# Hovilink.net
KiCad netlist of a schematic drawn in EAGLE
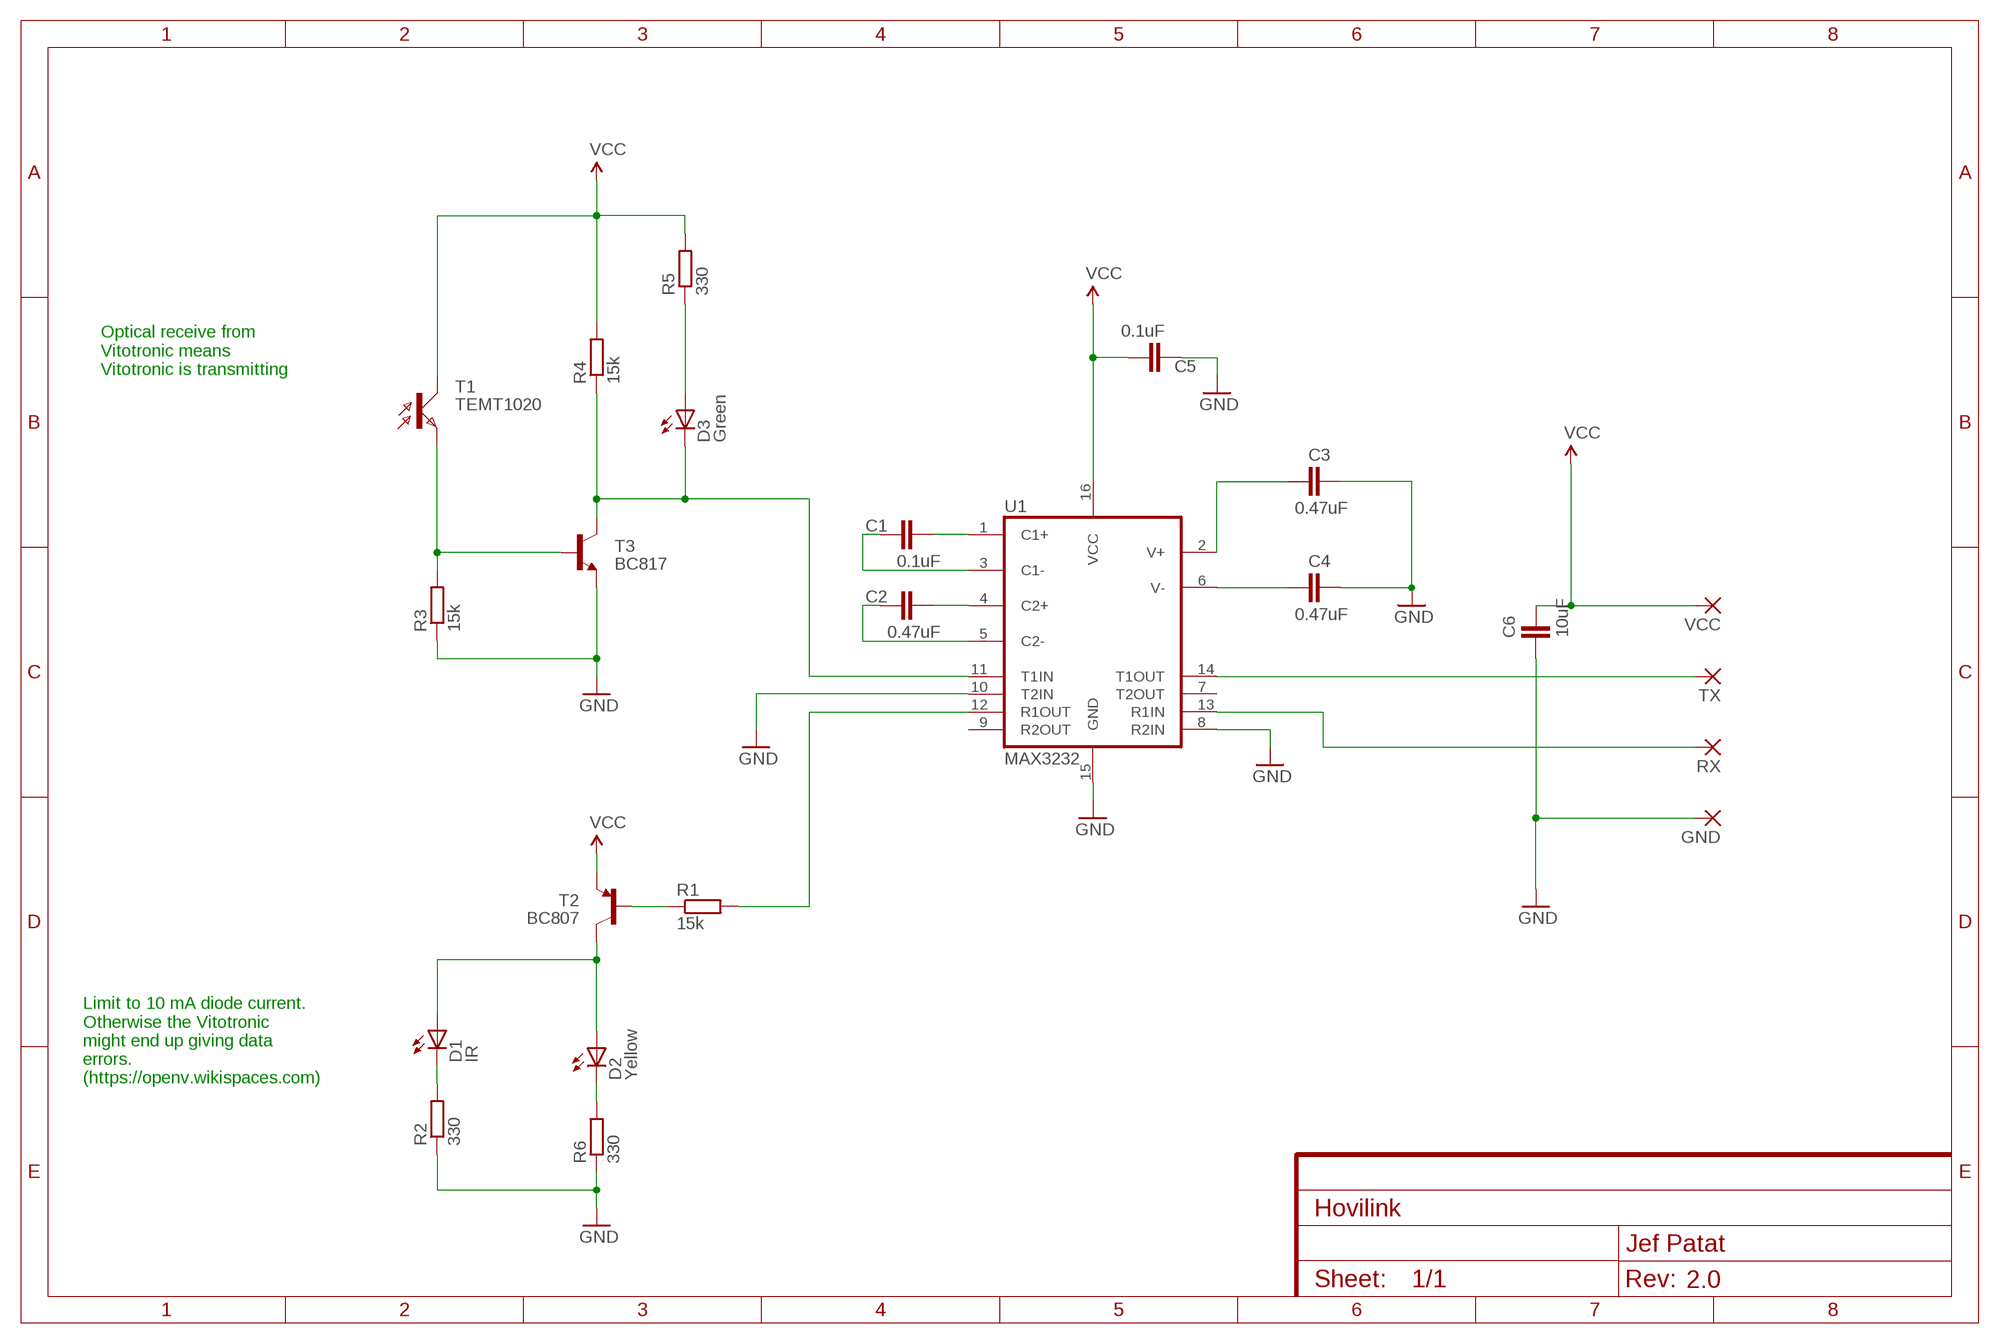
[diagram p0: schematic, sheet 1]

(export (version "E")
  (design (tool "Eeschema 10.0.6"))
  (components
    (comp (ref "C1")
      (value "0.1uF")
      (footprint "eagle-import:1206")
      (libsource (lib "eagle-import") (part "C1206"))
    )
    (comp (ref "C2")
      (value "0.47uF")
      (footprint "eagle-import:1206")
      (libsource (lib "eagle-import") (part "C1206"))
    )
    (comp (ref "C3")
      (value "0.47uF")
      (footprint "eagle-import:1206")
      (libsource (lib "eagle-import") (part "C1206"))
    )
    (comp (ref "C4")
      (value "0.47uF")
      (footprint "eagle-import:1206")
      (libsource (lib "eagle-import") (part "C1206"))
    )
    (comp (ref "C5")
      (value "0.1uF")
      (footprint "eagle-import:1206")
      (libsource (lib "eagle-import") (part "C1206"))
    )
    (comp (ref "C6")
      (value "10uF")
      (footprint "eagle-import:1206")
      (libsource (lib "eagle-import") (part "C1206"))
    )
    (comp (ref "D1")
      (value "TSMF1020")
      (footprint "eagle-import:TSMF1020")
      (libsource (lib "eagle-import") (part "TSMF1020"))
    )
    (comp (ref "D2")
      (value "KP-2012SYCK")
      (footprint "eagle-import:KNIGHTBRIGHT_2.0X1.25_SMD_LED")
      (libsource (lib "eagle-import") (part "KP-2012SYCK"))
    )
    (comp (ref "D3")
      (value "KP-2012CGCK")
      (footprint "eagle-import:KNIGHTBRIGHT_2.0X1.25_SMD_LED")
      (libsource (lib "eagle-import") (part "KP-2012CGCK"))
    )
    (comp (ref "GND")
      (value "WIREPAD_2,54/1,3")
      (footprint "eagle-import:WIREPAD_2,54_1,3")
      (libsource (lib "eagle-import") (part "WIREPAD_2,54/1,3"))
    )
    (comp (ref "R1")
      (value "15k")
      (footprint "eagle-import:1206")
      (libsource (lib "eagle-import") (part "R1206"))
    )
    (comp (ref "R2")
      (value "330")
      (footprint "eagle-import:1206")
      (libsource (lib "eagle-import") (part "R1206"))
    )
    (comp (ref "R3")
      (value "15k")
      (footprint "eagle-import:1206")
      (libsource (lib "eagle-import") (part "R1206"))
    )
    (comp (ref "R4")
      (value "15k")
      (footprint "eagle-import:1206")
      (libsource (lib "eagle-import") (part "R1206"))
    )
    (comp (ref "R5")
      (value "330")
      (footprint "eagle-import:1206")
      (libsource (lib "eagle-import") (part "R1206"))
    )
    (comp (ref "R6")
      (value "330")
      (footprint "eagle-import:1206")
      (libsource (lib "eagle-import") (part "R1206"))
    )
    (comp (ref "RX")
      (value "WIREPAD_2,54/1,3")
      (footprint "eagle-import:WIREPAD_2,54_1,3")
      (libsource (lib "eagle-import") (part "WIREPAD_2,54/1,3"))
    )
    (comp (ref "T1")
      (value "TEMT1020")
      (footprint "eagle-import:TEMT1020")
      (libsource (lib "eagle-import") (part "TEMT1020"))
    )
    (comp (ref "T2")
      (value "BC807")
      (footprint "eagle-import:SOT23_3")
      (libsource (lib "eagle-import") (part "BC807"))
    )
    (comp (ref "T3")
      (value "BC817")
      (footprint "eagle-import:SOT23_3")
      (libsource (lib "eagle-import") (part "BC817"))
    )
    (comp (ref "TX")
      (value "WIREPAD_2,54/1,3")
      (footprint "eagle-import:WIREPAD_2,54_1,3")
      (libsource (lib "eagle-import") (part "WIREPAD_2,54/1,3"))
    )
    (comp (ref "U1")
      (value "MAX3232")
      (footprint "eagle-import:SOIC16")
      (libsource (lib "eagle-import") (part "MAX3232"))
    )
    (comp (ref "VCC")
      (value "WIREPAD_2,54/1,3")
      (footprint "eagle-import:WIREPAD_2,54_1,3")
      (libsource (lib "eagle-import") (part "WIREPAD_2,54/1,3"))
    )
  )
  (nets
    (net (code "1") (name "GND") (class "Default")
      (node (ref "C3") (pin "2") (pinfunction "2_2") (pintype "passive"))
      (node (ref "C4") (pin "2") (pinfunction "2_2") (pintype "passive"))
      (node (ref "C5") (pin "1") (pinfunction "1_1") (pintype "passive"))
      (node (ref "C6") (pin "1") (pinfunction "1_1") (pintype "passive"))
      (node (ref "GND") (pin "1") (pinfunction "P_1") (pintype "passive"))
      (node (ref "R2") (pin "1") (pinfunction "1_1") (pintype "passive"))
      (node (ref "R3") (pin "1") (pinfunction "1_1") (pintype "passive"))
      (node (ref "R6") (pin "1") (pinfunction "1_1") (pintype "passive"))
      (node (ref "T3") (pin "2") (pinfunction "E_2") (pintype "passive"))
      (node (ref "U1") (pin "10") (pinfunction "T2IN_10") (pintype "input"))
      (node (ref "U1") (pin "15") (pinfunction "GND_15") (pintype "bidirectional"))
      (node (ref "U1") (pin "8") (pinfunction "R2IN_8") (pintype "input"))
    )
    (net (code "2") (name "Net-(D1-A)") (class "Default")
      (node (ref "D1") (pin "P$2") (pinfunction "A_P$2") (pintype "passive"))
      (node (ref "D2") (pin "P$1") (pinfunction "A_P$1") (pintype "passive"))
      (node (ref "T2") (pin "3") (pinfunction "C_3") (pintype "passive"))
    )
    (net (code "3") (name "Net-(D1-C)") (class "Default")
      (node (ref "D1") (pin "P$1") (pinfunction "C_P$1") (pintype "passive"))
      (node (ref "R2") (pin "2") (pinfunction "2_2") (pintype "passive"))
    )
    (net (code "4") (name "Net-(D2-C)") (class "Default")
      (node (ref "D2") (pin "P$2") (pinfunction "C_P$2") (pintype "passive"))
      (node (ref "R6") (pin "2") (pinfunction "2_2") (pintype "passive"))
    )
    (net (code "5") (name "Net-(D3-A)") (class "Default")
      (node (ref "D3") (pin "P$1") (pinfunction "A_P$1") (pintype "passive"))
      (node (ref "R5") (pin "1") (pinfunction "1_1") (pintype "passive"))
    )
    (net (code "6") (name "Net-(D3-C)") (class "Default")
      (node (ref "D3") (pin "P$2") (pinfunction "C_P$2") (pintype "passive"))
      (node (ref "R4") (pin "1") (pinfunction "1_1") (pintype "passive"))
      (node (ref "T3") (pin "3") (pinfunction "C_3") (pintype "passive"))
      (node (ref "U1") (pin "11") (pinfunction "T1IN_11") (pintype "input"))
    )
    (net (code "7") (name "Net-(RX-P)") (class "Default")
      (node (ref "RX") (pin "1") (pinfunction "P_1") (pintype "passive"))
      (node (ref "U1") (pin "13") (pinfunction "R1IN_13") (pintype "input"))
    )
    (net (code "8") (name "Net-(T1-E)") (class "Default")
      (node (ref "R3") (pin "2") (pinfunction "2_2") (pintype "passive"))
      (node (ref "T1") (pin "P$2") (pinfunction "E_P$2") (pintype "passive"))
      (node (ref "T3") (pin "1") (pinfunction "B_1") (pintype "passive"))
    )
    (net (code "9") (name "Net-(T2-B)") (class "Default")
      (node (ref "R1") (pin "1") (pinfunction "1_1") (pintype "passive"))
      (node (ref "T2") (pin "1") (pinfunction "B_1") (pintype "passive"))
    )
    (net (code "10") (name "Net-(TX-P)") (class "Default")
      (node (ref "TX") (pin "1") (pinfunction "P_1") (pintype "passive"))
      (node (ref "U1") (pin "14") (pinfunction "T1OUT_14") (pintype "output"))
    )
    (net (code "11") (name "Net-(U1-C1+)") (class "Default")
      (node (ref "C1") (pin "2") (pinfunction "2_2") (pintype "passive"))
      (node (ref "U1") (pin "1") (pinfunction "C1+_1") (pintype "bidirectional"))
    )
    (net (code "12") (name "Net-(U1-C1-)") (class "Default")
      (node (ref "C1") (pin "1") (pinfunction "1_1") (pintype "passive"))
      (node (ref "U1") (pin "3") (pinfunction "C1-_3") (pintype "bidirectional"))
    )
    (net (code "13") (name "Net-(U1-C2+)") (class "Default")
      (node (ref "C2") (pin "2") (pinfunction "2_2") (pintype "passive"))
      (node (ref "U1") (pin "4") (pinfunction "C2+_4") (pintype "bidirectional"))
    )
    (net (code "14") (name "Net-(U1-C2-)") (class "Default")
      (node (ref "C2") (pin "1") (pinfunction "1_1") (pintype "passive"))
      (node (ref "U1") (pin "5") (pinfunction "C2-_5") (pintype "bidirectional"))
    )
    (net (code "15") (name "Net-(U1-R1OUT)") (class "Default")
      (node (ref "R1") (pin "2") (pinfunction "2_2") (pintype "passive"))
      (node (ref "U1") (pin "12") (pinfunction "R1OUT_12") (pintype "output"))
    )
    (net (code "16") (name "Net-(U1-V+)") (class "Default")
      (node (ref "C3") (pin "1") (pinfunction "1_1") (pintype "passive"))
      (node (ref "U1") (pin "2") (pinfunction "V+_2") (pintype "bidirectional"))
    )
    (net (code "17") (name "Net-(U1-V-)") (class "Default")
      (node (ref "C4") (pin "1") (pinfunction "1_1") (pintype "passive"))
      (node (ref "U1") (pin "6") (pinfunction "V-_6") (pintype "bidirectional"))
    )
    (net (code "18") (name "VCC") (class "Default")
      (node (ref "C5") (pin "2") (pinfunction "2_2") (pintype "passive"))
      (node (ref "C6") (pin "2") (pinfunction "2_2") (pintype "passive"))
      (node (ref "R4") (pin "2") (pinfunction "2_2") (pintype "passive"))
      (node (ref "R5") (pin "2") (pinfunction "2_2") (pintype "passive"))
      (node (ref "T1") (pin "P$1") (pinfunction "C_P$1") (pintype "passive"))
      (node (ref "T2") (pin "2") (pinfunction "E_2") (pintype "passive"))
      (node (ref "U1") (pin "16") (pinfunction "VCC_16") (pintype "bidirectional"))
      (node (ref "VCC") (pin "1") (pinfunction "P_1") (pintype "passive"))
    )
    (net (code "19") (name "unconnected-(U1-R2OUT-Pad9)") (class "Default")
      (node (ref "U1") (pin "9") (pinfunction "R2OUT_9") (pintype "output"))
    )
    (net (code "20") (name "unconnected-(U1-T2OUT-Pad7)") (class "Default")
      (node (ref "U1") (pin "7") (pinfunction "T2OUT_7") (pintype "output"))
    )
  )
)
